# Aixcel_Tiny_Recon_Board_Page1.net
KiCad netlist of a schematic drawn in Altium Designer
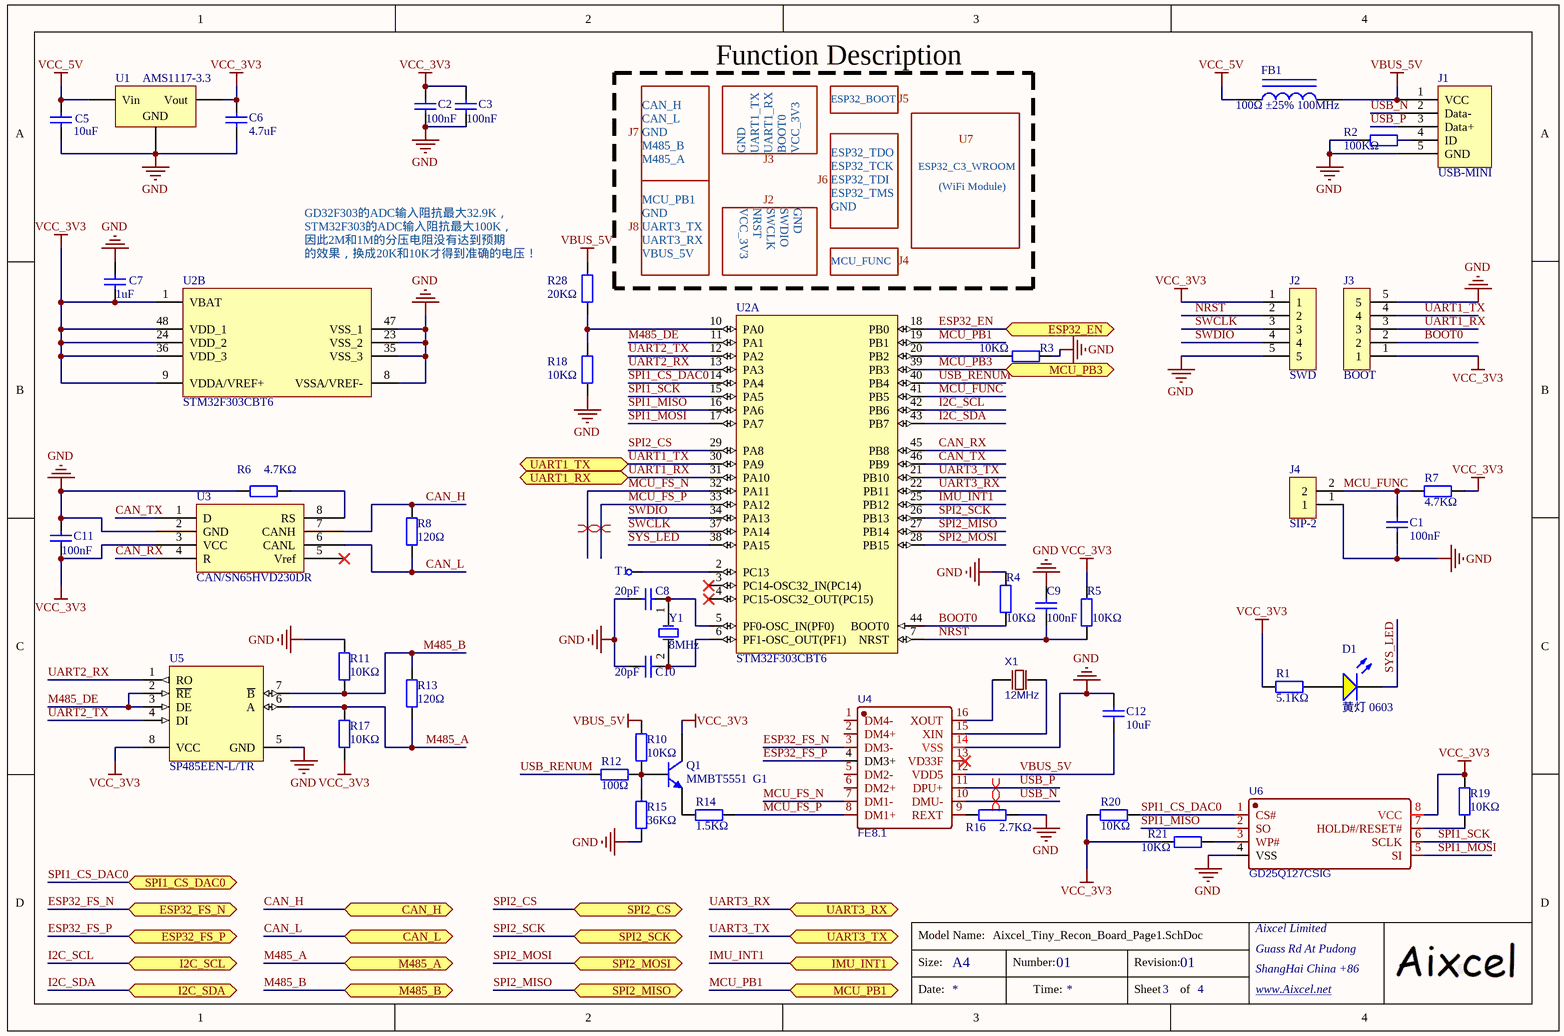
[diagram p0: Aixcel_Tiny_Recon_Board_Page1.SchDoc]

(export (version "E")
  (design (tool "Eeschema 10.0.6"))
  (components
    (comp (ref "C1")
      (value "100nF")
      (footprint "0603_C")
      (description "贴片电容")
      (libsource (lib "Miscellaneous Devices LC") (part "0603 100nF (104) 10% 50V"))
    )
    (comp (ref "C2")
      (value "100nF")
      (footprint "0603_C")
      (description "贴片电容")
      (libsource (lib "Miscellaneous Devices LC") (part "0603 100nF (104) 10% 50V"))
    )
    (comp (ref "C3")
      (value "100nF")
      (footprint "0603_C")
      (description "贴片电容")
      (libsource (lib "Miscellaneous Devices LC") (part "0603 100nF (104) 10% 50V"))
    )
    (comp (ref "C5")
      (value "10uF")
      (footprint "0603_C")
      (description "贴片电容")
      (libsource (lib "Miscellaneous Devices LC") (part "0603 10uF (106) 10% 10V"))
    )
    (comp (ref "C6")
      (value "4.7uF")
      (footprint "0603_C")
      (description "贴片电容")
      (libsource (lib "Miscellaneous Devices LC") (part "0603 4.7uF (475) 10% 16V"))
    )
    (comp (ref "C7")
      (value "1uF")
      (footprint "0603_C")
      (description "贴片电容")
      (libsource (lib "Miscellaneous Devices LC") (part "0603 1uF (105) 10% 50V"))
    )
    (comp (ref "C8")
      (value "20pF")
      (footprint "0603_C")
      (description "贴片电容")
      (libsource (lib "Miscellaneous Devices LC") (part "0603 20pF (200) 5% 50V"))
    )
    (comp (ref "C9")
      (value "100nF")
      (footprint "0603_C")
      (description "贴片电容")
      (libsource (lib "Miscellaneous Devices LC") (part "0603 100nF (104) 10% 50V"))
    )
    (comp (ref "C10")
      (value "20pF")
      (footprint "0603_C")
      (description "贴片电容")
      (libsource (lib "Miscellaneous Devices LC") (part "0603 20pF (200) 5% 50V"))
    )
    (comp (ref "C11")
      (value "100nF")
      (footprint "0603_C")
      (description "贴片电容")
      (libsource (lib "Miscellaneous Devices LC") (part "0603 100nF (104) 10% 50V"))
    )
    (comp (ref "C12")
      (value "10uF")
      (footprint "0603_C")
      (description "贴片电容")
      (libsource (lib "Miscellaneous Devices LC") (part "0603 10uF (106) 10% 10V"))
    )
    (comp (ref "D1")
      (value "黄灯 0603")
      (footprint "0603_LED_S1")
      (description "发光二极管")
      (libsource (lib "Miscellaneous Devices LC") (part "0603 黄灯"))
    )
    (comp (ref "FB1")
      (value "100Ω ±25% 100MHz")
      (footprint "0805_L")
      (description "贴片磁珠")
      (libsource (lib "Miscellaneous Devices LC") (part "0805 100Ω 25% 100MHz"))
    )
    (comp (ref "J1") (value "USB-MINI") (footprint "USB-MINI贴片") (libsource (lib "接插件") (part "USB-MINI")))
    (comp (ref "J2") (value "SWD") (footprint "ZH1.5-WS-5P") (libsource (lib "") (part "SIP-5_1")))
    (comp (ref "J3") (value "BOOT") (footprint "ZH1.5-WS-5P") (libsource (lib "接插件") (part "SIP-5")))
    (comp (ref "J4") (value "SIP-2") (footprint "TSW SMD-3*6*2.5") (libsource (lib "接插件") (part "SIP-2")))
    (comp (ref "Q1")
      (value "MMBT5551  G1")
      (footprint "SOT-23(SOT-23-3)")
      (description "三极管")
      (libsource (lib "Miscellaneous Devices LC") (part "SOT-23 MMBT5551  G1"))
    )
    (comp (ref "R1")
      (value "5.1KΩ")
      (footprint "0603_R")
      (description "贴片电阻")
      (libsource (lib "Miscellaneous Devices LC") (part "0603 5.1KΩ (5101) 1%"))
    )
    (comp (ref "R2")
      (value "100KΩ")
      (footprint "0603_R")
      (description "贴片电阻")
      (libsource (lib "Miscellaneous Devices LC") (part "0603 100KΩ (1003) 1%"))
    )
    (comp (ref "R3")
      (value "10KΩ")
      (footprint "0603_R")
      (description "贴片电阻")
      (libsource (lib "Miscellaneous Devices LC") (part "0603 10KΩ (1002) 1%"))
    )
    (comp (ref "R4")
      (value "10KΩ")
      (footprint "0603_R")
      (description "贴片电阻")
      (libsource (lib "") (part "0603 10KΩ (1002) 1%_2"))
    )
    (comp (ref "R5")
      (value "10KΩ")
      (footprint "0603_R")
      (description "贴片电阻")
      (libsource (lib "") (part "0603 10KΩ (1002) 1%_2"))
    )
    (comp (ref "R6")
      (value "4.7KΩ")
      (footprint "0603_R")
      (description "贴片电阻")
      (libsource (lib "Miscellaneous Devices LC") (part "0603 4.7KΩ (4701) 1%"))
    )
    (comp (ref "R7")
      (value "4.7KΩ")
      (footprint "0603_R")
      (description "贴片电阻")
      (libsource (lib "Miscellaneous Devices LC") (part "0603 4.7KΩ (4701) 1%"))
    )
    (comp (ref "R8")
      (value "120Ω")
      (footprint "0603_R")
      (description "贴片电阻")
      (libsource (lib "Miscellaneous Devices LC") (part "0603 120Ω (1200) 1%"))
    )
    (comp (ref "R10")
      (value "10KΩ")
      (footprint "0603_R")
      (description "贴片电阻")
      (libsource (lib "") (part "0603 10KΩ (1002) 1%_2"))
    )
    (comp (ref "R11")
      (value "10KΩ")
      (footprint "0603_R")
      (description "贴片电阻")
      (libsource (lib "") (part "0603 10KΩ (1002) 1%_2"))
    )
    (comp (ref "R12")
      (value "100Ω")
      (footprint "0603_R")
      (description "贴片电阻")
      (libsource (lib "Miscellaneous Devices LC") (part "0603 100Ω (1000) 1%"))
    )
    (comp (ref "R13")
      (value "120Ω")
      (footprint "0603_R")
      (description "贴片电阻")
      (libsource (lib "Miscellaneous Devices LC") (part "0603 120Ω (1200) 1%"))
    )
    (comp (ref "R14")
      (value "1.5KΩ")
      (footprint "0603_R")
      (description "贴片电阻")
      (libsource (lib "Miscellaneous Devices LC") (part "0603 1.5KΩ (1501) 1%"))
    )
    (comp (ref "R15")
      (value "36KΩ")
      (footprint "0603_R")
      (description "贴片电阻")
      (libsource (lib "Miscellaneous Devices LC") (part "0603 36KΩ (3602) 1%"))
    )
    (comp (ref "R16")
      (value "2.7KΩ")
      (footprint "0603_R")
      (description "贴片电阻")
      (libsource (lib "Miscellaneous Devices LC") (part "0603 2.7KΩ (2701) 1%"))
    )
    (comp (ref "R17")
      (value "10KΩ")
      (footprint "0603_R")
      (description "贴片电阻")
      (libsource (lib "") (part "0603 10KΩ (1002) 1%_2"))
    )
    (comp (ref "R18")
      (value "10KΩ")
      (footprint "0603_R")
      (description "贴片电阻")
      (libsource (lib "") (part "0603 10KΩ (1002) 1%_2"))
    )
    (comp (ref "R19")
      (value "10KΩ")
      (footprint "0603_R")
      (description "贴片电阻")
      (libsource (lib "") (part "0603 10KΩ (1002) 1%_1"))
    )
    (comp (ref "R20")
      (value "10KΩ")
      (footprint "0603_R")
      (description "贴片电阻")
      (libsource (lib "") (part "0603 10KΩ (1002) 1%_3"))
    )
    (comp (ref "R21")
      (value "10KΩ")
      (footprint "0603_R")
      (description "贴片电阻")
      (libsource (lib "Miscellaneous Devices LC") (part "0603 10KΩ (1002) 1%"))
    )
    (comp (ref "R28")
      (value "20KΩ")
      (footprint "0603_R")
      (description "贴片电阻")
      (libsource (lib "Miscellaneous Devices LC") (part "0603 20KΩ (2002) 1%"))
    )
    (comp (ref "T1")
      (value "CHECK")
      (footprint "CHECK-C")
      (description "测试点")
      (libsource (lib "fszhang") (part "CHECK"))
    )
    (comp (ref "U1")
      (value "AMS1117-3.3")
      (footprint "SOT-223")
      (description "低压差线性稳压(LDO)")
      (libsource (lib "Miscellaneous Devices LC") (part "SOT-223 AMS1117-3.3"))
    )
    (comp (ref "U2")
      (value "STM32F303CBT6")
      (footprint "STM-LQFP48_L")
      (libsource (lib "STMicroelectronics STM32 F3") (part "STM32F303CBT6"))
    )
    (comp (ref "U3")
      (value "CAN/SN65HVD230DR")
      (footprint "SOIC-8_150mil")
      (description "CAN")
      (libsource (lib "Miscellaneous Devices LC") (part "CAN/SN65HVD230DR_[C12084]"))
    )
    (comp (ref "U4")
      (value "FE8.1")
      (footprint "SSOP-16_L4.9-W3.9-P0.64-LS6.0-BL")
      (fields (field (name "CONTRIBUTOR") "私有工程"))
      (libsource (lib "FE8.1") (part "FE8.1"))
    )
    (comp (ref "U5")
      (value "SP485EEN-L/TR")
      (footprint "SOIC-8_150mil")
      (description "RS-485/RS-422")
      (libsource (lib "Miscellaneous Devices LC") (part "SP485EEN-L/TR_[C6855]"))
    )
    (comp (ref "U6")
      (value "GD25Q127CSIG")
      (footprint "GD25Q127CSIG")
      (fields (field (name "BOM_SUPPLIER PART") "C79079"))
      (libsource (lib "其他") (part "GD25Q127CSIG"))
    )
    (comp (ref "X1")
      (value "12MHz")
      (footprint "12MHz")
      (fields
        (field (name "BOM_SUPPLIER PART") "C33728")
        (field (name "BOM_MANUFACTURER PART") "X503212MSD2GC")
      )
      (libsource (lib "其他") (part "12MHz"))
    )
    (comp (ref "Y1")
      (value "8MHz")
      (footprint "SMD-5032_2P")
      (description "贴片晶振")
      (libsource (lib "Miscellaneous Devices LC") (part "SMD-5032_2P 8MHz 20ppm 20pF"))
    )
  )
  (nets
    (net (code "1") (name "/BOOT0") (class "Default")
      (node (ref "J3") (pin "2") (pinfunction "2_2") (pintype "passive"))
      (node (ref "R4") (pin "1") (pinfunction "1_1") (pintype "passive"))
      (node (ref "U2") (pin "44") (pinfunction "BOOT0_44") (pintype "input"))
    )
    (net (code "2") (name "/CAN_H") (class "Default")
      (node (ref "R8") (pin "2") (pinfunction "2_2") (pintype "passive"))
      (node (ref "U3") (pin "7") (pinfunction "CANH_7") (pintype "passive"))
    )
    (net (code "3") (name "/CAN_L") (class "Default")
      (node (ref "R8") (pin "1") (pinfunction "1_1") (pintype "passive"))
      (node (ref "U3") (pin "6") (pinfunction "CANL_6") (pintype "passive"))
    )
    (net (code "4") (name "/CAN_RX") (class "Default")
      (node (ref "U2") (pin "45") (pinfunction "PB8_45") (pintype "bidirectional"))
      (node (ref "U3") (pin "4") (pinfunction "R_4") (pintype "passive"))
    )
    (net (code "5") (name "/CAN_TX") (class "Default")
      (node (ref "U2") (pin "46") (pinfunction "PB9_46") (pintype "bidirectional"))
      (node (ref "U3") (pin "1") (pinfunction "D_1") (pintype "passive"))
    )
    (net (code "6") (name "/ESP32_EN") (class "Default")
      (node (ref "U2") (pin "18") (pinfunction "PB0_18") (pintype "bidirectional"))
    )
    (net (code "7") (name "/ESP32_FS_N") (class "Default")
      (node (ref "U4") (pin "3") (pinfunction "DM3-_3") (pintype "passive"))
    )
    (net (code "8") (name "/ESP32_FS_P") (class "Default")
      (node (ref "U4") (pin "4") (pinfunction "DM3+_4") (pintype "passive"))
    )
    (net (code "9") (name "/I2C_SCL") (class "Default")
      (node (ref "U2") (pin "42") (pinfunction "PB6_42") (pintype "bidirectional"))
    )
    (net (code "10") (name "/I2C_SDA") (class "Default")
      (node (ref "U2") (pin "43") (pinfunction "PB7_43") (pintype "bidirectional"))
    )
    (net (code "11") (name "/IMU_INT1") (class "Default")
      (node (ref "U2") (pin "25") (pinfunction "PB12_25") (pintype "bidirectional"))
    )
    (net (code "12") (name "/M485_A") (class "Default")
      (node (ref "R13") (pin "1") (pinfunction "1_1") (pintype "passive"))
      (node (ref "R17") (pin "2") (pinfunction "2_2") (pintype "passive"))
      (node (ref "U5") (pin "6") (pinfunction "A_6") (pintype "bidirectional"))
    )
    (net (code "13") (name "/M485_B") (class "Default")
      (node (ref "R11") (pin "1") (pinfunction "1_1") (pintype "passive"))
      (node (ref "R13") (pin "2") (pinfunction "2_2") (pintype "passive"))
      (node (ref "U5") (pin "7") (pinfunction "~{B}_7") (pintype "bidirectional"))
    )
    (net (code "14") (name "/M485_DE") (class "Default")
      (node (ref "U2") (pin "11") (pinfunction "PA1_11") (pintype "bidirectional"))
      (node (ref "U5") (pin "2") (pinfunction "~{RE}_2") (pintype "input"))
      (node (ref "U5") (pin "3") (pinfunction "DE_3") (pintype "input"))
    )
    (net (code "15") (name "/MCU_FS_N") (class "Default")
      (node (ref "U2") (pin "32") (pinfunction "PA11_32") (pintype "bidirectional"))
      (node (ref "U4") (pin "7") (pinfunction "DM1-_7") (pintype "passive"))
    )
    (net (code "16") (name "/MCU_FS_P") (class "Default")
      (node (ref "R14") (pin "1") (pinfunction "1_1") (pintype "passive"))
      (node (ref "U2") (pin "33") (pinfunction "PA12_33") (pintype "bidirectional"))
      (node (ref "U4") (pin "8") (pinfunction "DM1+_8") (pintype "passive"))
    )
    (net (code "17") (name "/MCU_FUNC") (class "Default")
      (node (ref "C1") (pin "2") (pinfunction "2_2") (pintype "passive"))
      (node (ref "J4") (pin "2") (pinfunction "2_2") (pintype "passive"))
      (node (ref "R7") (pin "1") (pinfunction "1_1") (pintype "passive"))
      (node (ref "U2") (pin "41") (pinfunction "PB5_41") (pintype "bidirectional"))
    )
    (net (code "18") (name "/MCU_PB1") (class "Default")
      (node (ref "U2") (pin "19") (pinfunction "PB1_19") (pintype "bidirectional"))
    )
    (net (code "19") (name "/MCU_PB3") (class "Default")
      (node (ref "U2") (pin "39") (pinfunction "PB3_39") (pintype "bidirectional"))
    )
    (net (code "20") (name "/NRST") (class "Default")
      (node (ref "C9") (pin "1") (pinfunction "1_1") (pintype "passive"))
      (node (ref "J2") (pin "2") (pinfunction "2_2") (pintype "passive"))
      (node (ref "R5") (pin "1") (pinfunction "1_1") (pintype "passive"))
      (node (ref "U2") (pin "7") (pinfunction "NRST_7") (pintype "bidirectional"))
    )
    (net (code "21") (name "/SPI1_CS_DAC0") (class "Default")
      (node (ref "R20") (pin "2") (pinfunction "2_2") (pintype "passive"))
      (node (ref "U2") (pin "14") (pinfunction "PA4_14") (pintype "bidirectional"))
      (node (ref "U6") (pin "1") (pinfunction "CS#_1") (pintype "passive"))
    )
    (net (code "22") (name "/SPI1_MISO") (class "Default")
      (node (ref "U2") (pin "16") (pinfunction "PA6_16") (pintype "bidirectional"))
      (node (ref "U6") (pin "2") (pinfunction "SO_2") (pintype "passive"))
    )
    (net (code "23") (name "/SPI1_MOSI") (class "Default")
      (node (ref "U2") (pin "17") (pinfunction "PA7_17") (pintype "bidirectional"))
      (node (ref "U6") (pin "5") (pinfunction "SI_5") (pintype "passive"))
    )
    (net (code "24") (name "/SPI1_SCK") (class "Default")
      (node (ref "U2") (pin "15") (pinfunction "PA5_15") (pintype "bidirectional"))
      (node (ref "U6") (pin "6") (pinfunction "SCLK_6") (pintype "passive"))
    )
    (net (code "25") (name "/SPI2_CS") (class "Default")
      (node (ref "U2") (pin "29") (pinfunction "PA8_29") (pintype "bidirectional"))
    )
    (net (code "26") (name "/SPI2_MISO") (class "Default")
      (node (ref "U2") (pin "27") (pinfunction "PB14_27") (pintype "bidirectional"))
    )
    (net (code "27") (name "/SPI2_MOSI") (class "Default")
      (node (ref "U2") (pin "28") (pinfunction "PB15_28") (pintype "bidirectional"))
    )
    (net (code "28") (name "/SPI2_SCK") (class "Default")
      (node (ref "U2") (pin "26") (pinfunction "PB13_26") (pintype "bidirectional"))
    )
    (net (code "29") (name "/SWCLK") (class "Default")
      (node (ref "J2") (pin "3") (pinfunction "3_3") (pintype "passive"))
      (node (ref "U2") (pin "37") (pinfunction "PA14_37") (pintype "bidirectional"))
    )
    (net (code "30") (name "/SWDIO") (class "Default")
      (node (ref "J2") (pin "4") (pinfunction "4_4") (pintype "passive"))
      (node (ref "U2") (pin "34") (pinfunction "PA13_34") (pintype "bidirectional"))
    )
    (net (code "31") (name "/SYS_LED") (class "Default")
      (node (ref "D1") (pin "K") (pinfunction "K_K") (pintype "passive"))
      (node (ref "U2") (pin "38") (pinfunction "PA15_38") (pintype "bidirectional"))
    )
    (net (code "32") (name "/UART1_RX") (class "Default")
      (node (ref "J3") (pin "3") (pinfunction "3_3") (pintype "passive"))
      (node (ref "U2") (pin "31") (pinfunction "PA10_31") (pintype "bidirectional"))
    )
    (net (code "33") (name "/UART1_TX") (class "Default")
      (node (ref "J3") (pin "4") (pinfunction "4_4") (pintype "passive"))
      (node (ref "U2") (pin "30") (pinfunction "PA9_30") (pintype "bidirectional"))
    )
    (net (code "34") (name "/UART2_RX") (class "Default")
      (node (ref "U2") (pin "13") (pinfunction "PA3_13") (pintype "bidirectional"))
      (node (ref "U5") (pin "1") (pinfunction "RO_1") (pintype "output"))
    )
    (net (code "35") (name "/UART2_TX") (class "Default")
      (node (ref "U2") (pin "12") (pinfunction "PA2_12") (pintype "bidirectional"))
      (node (ref "U5") (pin "4") (pinfunction "DI_4") (pintype "input"))
    )
    (net (code "36") (name "/UART3_RX") (class "Default")
      (node (ref "U2") (pin "22") (pinfunction "PB11_22") (pintype "bidirectional"))
    )
    (net (code "37") (name "/UART3_TX") (class "Default")
      (node (ref "U2") (pin "21") (pinfunction "PB10_21") (pintype "bidirectional"))
    )
    (net (code "38") (name "/USB_N") (class "Default")
      (node (ref "J1") (pin "2") (pinfunction "Data-_2") (pintype "passive"))
      (node (ref "U4") (pin "10") (pinfunction "DMU-_10") (pintype "passive"))
    )
    (net (code "39") (name "/USB_P") (class "Default")
      (node (ref "J1") (pin "3") (pinfunction "Data+_3") (pintype "passive"))
      (node (ref "U4") (pin "11") (pinfunction "DPU+_11") (pintype "passive"))
    )
    (net (code "40") (name "/USB_RENUM") (class "Default")
      (node (ref "R12") (pin "1") (pinfunction "1_1") (pintype "passive"))
      (node (ref "U2") (pin "40") (pinfunction "PB4_40") (pintype "bidirectional"))
    )
    (net (code "41") (name "GND") (class "Default")
      (node (ref "C1") (pin "1") (pinfunction "1_1") (pintype "passive"))
      (node (ref "C10") (pin "1") (pinfunction "1_1") (pintype "passive"))
      (node (ref "C11") (pin "2") (pinfunction "2_2") (pintype "passive"))
      (node (ref "C12") (pin "2") (pinfunction "2_2") (pintype "passive"))
      (node (ref "C2") (pin "2") (pinfunction "2_2") (pintype "passive"))
      (node (ref "C3") (pin "2") (pinfunction "2_2") (pintype "passive"))
      (node (ref "C5") (pin "1") (pinfunction "1_1") (pintype "passive"))
      (node (ref "C6") (pin "1") (pinfunction "1_1") (pintype "passive"))
      (node (ref "C7") (pin "2") (pinfunction "2_2") (pintype "passive"))
      (node (ref "C8") (pin "1") (pinfunction "1_1") (pintype "passive"))
      (node (ref "C9") (pin "2") (pinfunction "2_2") (pintype "passive"))
      (node (ref "J1") (pin "5") (pinfunction "GND_5") (pintype "passive"))
      (node (ref "J2") (pin "5") (pinfunction "5_5") (pintype "passive"))
      (node (ref "J3") (pin "5") (pinfunction "5_5") (pintype "passive"))
      (node (ref "J4") (pin "1") (pinfunction "1_1") (pintype "passive"))
      (node (ref "R11") (pin "2") (pinfunction "2_2") (pintype "passive"))
      (node (ref "R15") (pin "1") (pinfunction "1_1") (pintype "passive"))
      (node (ref "R16") (pin "2") (pinfunction "2_2") (pintype "passive"))
      (node (ref "R18") (pin "1") (pinfunction "1_1") (pintype "passive"))
      (node (ref "R2") (pin "1") (pinfunction "1_1") (pintype "passive"))
      (node (ref "R3") (pin "1") (pinfunction "1_1") (pintype "passive"))
      (node (ref "R4") (pin "2") (pinfunction "2_2") (pintype "passive"))
      (node (ref "R6") (pin "1") (pinfunction "1_1") (pintype "passive"))
      (node (ref "U1") (pin "1") (pinfunction "GND_1") (pintype "passive"))
      (node (ref "U2") (pin "23") (pinfunction "VSS_2_23") (pintype "power_in"))
      (node (ref "U2") (pin "35") (pinfunction "VSS_3_35") (pintype "power_in"))
      (node (ref "U2") (pin "47") (pinfunction "VSS_1_47") (pintype "power_in"))
      (node (ref "U2") (pin "8") (pinfunction "VSSA/VREF-_8") (pintype "power_in"))
      (node (ref "U3") (pin "2") (pinfunction "GND_2") (pintype "passive"))
      (node (ref "U4") (pin "14") (pinfunction "VSS_14") (pintype "passive"))
      (node (ref "U5") (pin "5") (pinfunction "GND_5") (pintype "power_in"))
      (node (ref "U6") (pin "4") (pinfunction "VSS_4") (pintype "passive"))
    )
    (net (code "42") (name "Net-(D1-PadA)") (class "Default")
      (node (ref "D1") (pin "A") (pinfunction "A_A") (pintype "passive"))
      (node (ref "R1") (pin "2") (pinfunction "2_2") (pintype "passive"))
    )
    (net (code "43") (name "Net-(J1-ID)") (class "Default")
      (node (ref "J1") (pin "4") (pinfunction "ID_4") (pintype "passive"))
      (node (ref "R2") (pin "2") (pinfunction "2_2") (pintype "passive"))
    )
    (net (code "44") (name "Net-(Q1-B)") (class "Default")
      (node (ref "Q1") (pin "1") (pinfunction "B_1") (pintype "passive"))
      (node (ref "R10") (pin "1") (pinfunction "1_1") (pintype "passive"))
      (node (ref "R12") (pin "2") (pinfunction "2_2") (pintype "passive"))
      (node (ref "R15") (pin "2") (pinfunction "2_2") (pintype "passive"))
    )
    (net (code "45") (name "Net-(Q1-E)") (class "Default")
      (node (ref "Q1") (pin "2") (pinfunction "E_2") (pintype "passive"))
      (node (ref "R14") (pin "2") (pinfunction "2_2") (pintype "passive"))
    )
    (net (code "46") (name "Net-(U2A-PA0)") (class "Default")
      (node (ref "R18") (pin "2") (pinfunction "2_2") (pintype "passive"))
      (node (ref "R28") (pin "1") (pinfunction "1_1") (pintype "passive"))
      (node (ref "U2") (pin "10") (pinfunction "PA0_10") (pintype "bidirectional"))
    )
    (net (code "47") (name "Net-(U2A-PB2)") (class "Default")
      (node (ref "R3") (pin "2") (pinfunction "2_2") (pintype "passive"))
      (node (ref "U2") (pin "20") (pinfunction "PB2_20") (pintype "bidirectional"))
    )
    (net (code "48") (name "Net-(U2A-PC13)") (class "Default")
      (node (ref "T1") (pin "1") (pinfunction "1_1") (pintype "passive"))
      (node (ref "U2") (pin "2") (pinfunction "PC13_2") (pintype "bidirectional"))
    )
    (net (code "49") (name "Net-(U2A-PF0-OSC_IN(PF0))") (class "Default")
      (node (ref "C8") (pin "2") (pinfunction "2_2") (pintype "passive"))
      (node (ref "U2") (pin "5") (pinfunction "PF0-OSC_IN(PF0)_5") (pintype "bidirectional"))
      (node (ref "Y1") (pin "1") (pinfunction "OSC1_1") (pintype "passive"))
    )
    (net (code "50") (name "Net-(U2A-PF1-OSC_OUT(PF1))") (class "Default")
      (node (ref "C10") (pin "2") (pinfunction "2_2") (pintype "passive"))
      (node (ref "U2") (pin "6") (pinfunction "PF1-OSC_OUT(PF1)_6") (pintype "bidirectional"))
      (node (ref "Y1") (pin "2") (pinfunction "OSC2_2") (pintype "passive"))
    )
    (net (code "51") (name "Net-(U3-RS)") (class "Default")
      (node (ref "R6") (pin "2") (pinfunction "2_2") (pintype "passive"))
      (node (ref "U3") (pin "8") (pinfunction "RS_8") (pintype "passive"))
    )
    (net (code "52") (name "Net-(U4-REXT)") (class "Default")
      (node (ref "R16") (pin "1") (pinfunction "1_1") (pintype "passive"))
      (node (ref "U4") (pin "9") (pinfunction "REXT_9") (pintype "passive"))
    )
    (net (code "53") (name "Net-(U4-XIN)") (class "Default")
      (node (ref "U4") (pin "15") (pinfunction "XIN_15") (pintype "passive"))
      (node (ref "X1") (pin "2") (pinfunction "OSC2_2") (pintype "passive"))
    )
    (net (code "54") (name "Net-(U4-XOUT)") (class "Default")
      (node (ref "U4") (pin "16") (pinfunction "XOUT_16") (pintype "passive"))
      (node (ref "X1") (pin "1") (pinfunction "OSC1_1") (pintype "passive"))
    )
    (net (code "55") (name "Net-(U6-HOLD#{slash}RESET#)") (class "Default")
      (node (ref "R19") (pin "2") (pinfunction "2_2") (pintype "passive"))
      (node (ref "U6") (pin "7") (pinfunction "HOLD#/RESET#_7") (pintype "passive"))
    )
    (net (code "56") (name "Net-(U6-WP#)") (class "Default")
      (node (ref "R21") (pin "1") (pinfunction "1_1") (pintype "passive"))
      (node (ref "U6") (pin "3") (pinfunction "WP#_3") (pintype "passive"))
    )
    (net (code "57") (name "VBUS_5V") (class "Default")
      (node (ref "C12") (pin "1") (pinfunction "1_1") (pintype "passive"))
      (node (ref "FB1") (pin "2") (pinfunction "2_2") (pintype "passive"))
      (node (ref "J1") (pin "1") (pinfunction "VCC_1") (pintype "passive"))
      (node (ref "R10") (pin "2") (pinfunction "2_2") (pintype "passive"))
      (node (ref "R28") (pin "2") (pinfunction "2_2") (pintype "passive"))
      (node (ref "U4") (pin "12") (pinfunction "VDD5_12") (pintype "passive"))
    )
    (net (code "58") (name "VCC_3V3") (class "Default")
      (node (ref "C11") (pin "1") (pinfunction "1_1") (pintype "passive"))
      (node (ref "C2") (pin "1") (pinfunction "1_1") (pintype "passive"))
      (node (ref "C3") (pin "1") (pinfunction "1_1") (pintype "passive"))
      (node (ref "C6") (pin "2") (pinfunction "2_2") (pintype "passive"))
      (node (ref "C7") (pin "1") (pinfunction "1_1") (pintype "passive"))
      (node (ref "J2") (pin "1") (pinfunction "1_1") (pintype "passive"))
      (node (ref "J3") (pin "1") (pinfunction "1_1") (pintype "passive"))
      (node (ref "Q1") (pin "3") (pinfunction "C_3") (pintype "passive"))
      (node (ref "R1") (pin "1") (pinfunction "1_1") (pintype "passive"))
      (node (ref "R17") (pin "1") (pinfunction "1_1") (pintype "passive"))
      (node (ref "R19") (pin "1") (pinfunction "1_1") (pintype "passive"))
      (node (ref "R20") (pin "1") (pinfunction "1_1") (pintype "passive"))
      (node (ref "R21") (pin "2") (pinfunction "2_2") (pintype "passive"))
      (node (ref "R5") (pin "2") (pinfunction "2_2") (pintype "passive"))
      (node (ref "R7") (pin "2") (pinfunction "2_2") (pintype "passive"))
      (node (ref "U1") (pin "2") (pinfunction "Vout_2") (pintype "passive"))
      (node (ref "U2") (pin "1") (pinfunction "VBAT_1") (pintype "power_in"))
      (node (ref "U2") (pin "24") (pinfunction "VDD_2_24") (pintype "power_in"))
      (node (ref "U2") (pin "36") (pinfunction "VDD_3_36") (pintype "power_in"))
      (node (ref "U2") (pin "48") (pinfunction "VDD_1_48") (pintype "power_in"))
      (node (ref "U2") (pin "9") (pinfunction "VDDA/VREF+_9") (pintype "power_in"))
      (node (ref "U3") (pin "3") (pinfunction "VCC_3") (pintype "passive"))
      (node (ref "U5") (pin "8") (pinfunction "VCC_8") (pintype "power_in"))
      (node (ref "U6") (pin "8") (pinfunction "VCC_8") (pintype "passive"))
    )
    (net (code "59") (name "VCC_5V") (class "Default")
      (node (ref "C5") (pin "2") (pinfunction "2_2") (pintype "passive"))
      (node (ref "FB1") (pin "1") (pinfunction "1_1") (pintype "passive"))
      (node (ref "U1") (pin "3") (pinfunction "Vin_3") (pintype "passive"))
    )
    (net (code "60") (name "unconnected-(U2A-PC14-OSC32_IN(PC14)-Pad3)") (class "Default")
      (node (ref "U2") (pin "3") (pinfunction "PC14-OSC32_IN(PC14)_3") (pintype "bidirectional+no_connect"))
    )
    (net (code "61") (name "unconnected-(U2A-PC15-OSC32_OUT(PC15)-Pad4)") (class "Default")
      (node (ref "U2") (pin "4") (pinfunction "PC15-OSC32_OUT(PC15)_4") (pintype "bidirectional+no_connect"))
    )
    (net (code "62") (name "unconnected-(U3-Vref-Pad5)") (class "Default")
      (node (ref "U3") (pin "5") (pinfunction "Vref_5") (pintype "passive+no_connect"))
    )
    (net (code "63") (name "unconnected-(U4-DM2+-Pad6)") (class "Default")
      (node (ref "U4") (pin "6") (pinfunction "DM2+_6") (pintype "passive"))
    )
    (net (code "64") (name "unconnected-(U4-DM2--Pad5)") (class "Default")
      (node (ref "U4") (pin "5") (pinfunction "DM2-_5") (pintype "passive"))
    )
    (net (code "65") (name "unconnected-(U4-DM4+-Pad2)") (class "Default")
      (node (ref "U4") (pin "2") (pinfunction "DM4+_2") (pintype "passive"))
    )
    (net (code "66") (name "unconnected-(U4-DM4--Pad1)") (class "Default")
      (node (ref "U4") (pin "1") (pinfunction "DM4-_1") (pintype "passive"))
    )
    (net (code "67") (name "unconnected-(U4-VD33F-Pad13)") (class "Default")
      (node (ref "U4") (pin "13") (pinfunction "VD33F_13") (pintype "passive+no_connect"))
    )
  )
)
